# control_boardv15.net
KiCad netlist of a schematic drawn in EAGLE
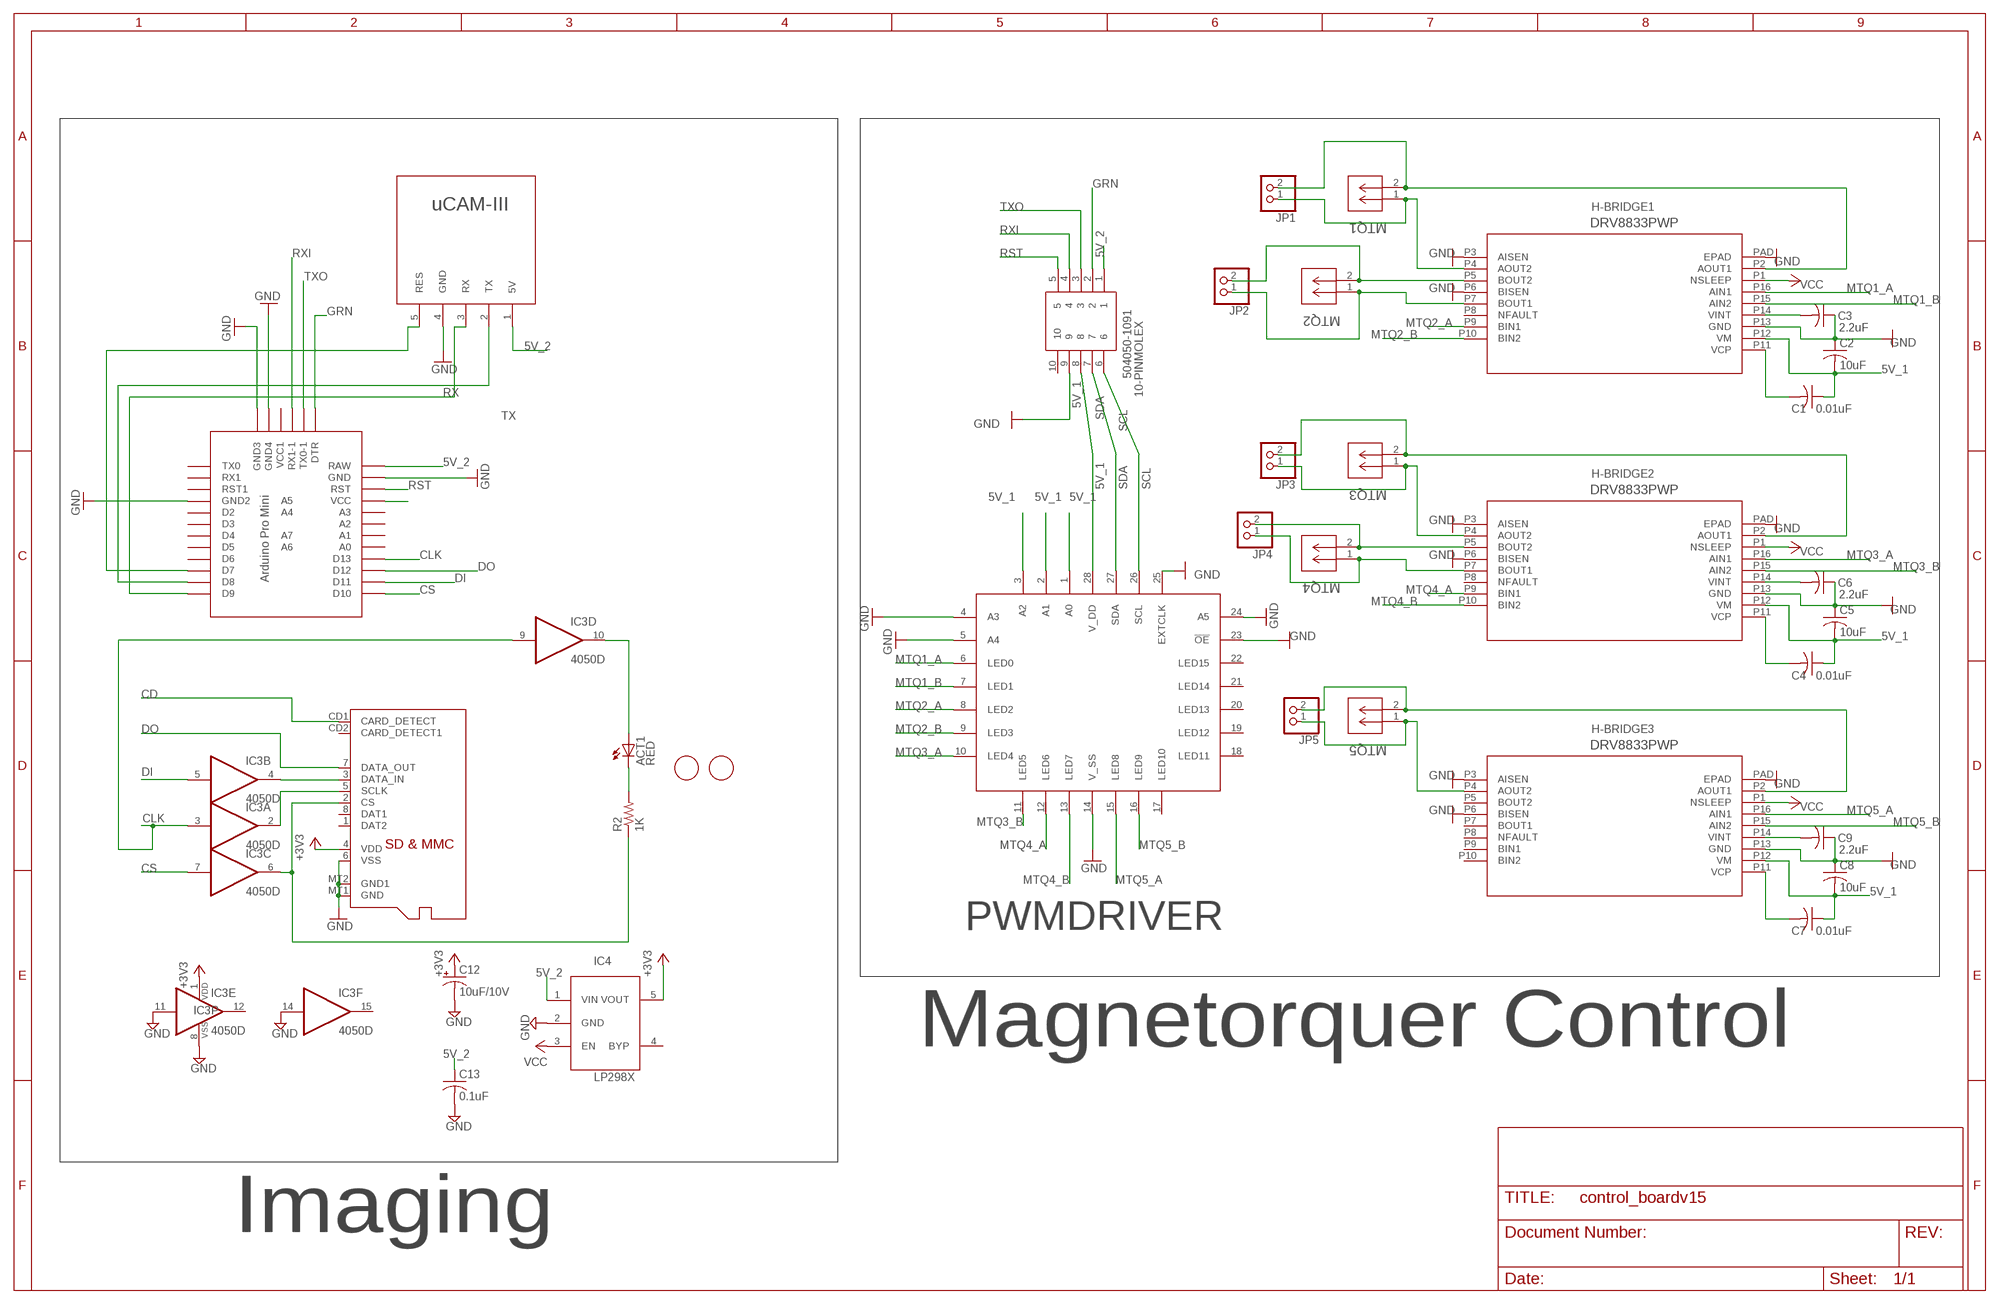
[diagram p0: schematic, sheet 1]

(export (version "E")
  (design (tool "Eeschema 10.0.6"))
  (components
    (comp (ref "10-PINMOLEX")
      (value "504050-1091")
      (footprint "eagle-import:504050-1091")
      (fields (field (name "MOUSER_PART_NUMBER") "538-504050-1091"))
      (libsource (lib "eagle-import") (part "504050-1091"))
    )
    (comp (ref "ACT1")
      (value "RED")
      (footprint "eagle-import:CHIP-LED0805")
      (libsource (lib "eagle-import") (part "LEDCHIP-LED0805"))
    )
    (comp (ref "C1")
      (value "0.01uF")
      (footprint "eagle-import:C0603K")
      (libsource (lib "eagle-import") (part "rcl_334_C-USC0603K"))
    )
    (comp (ref "C2")
      (value "10uF")
      (footprint "eagle-import:C1210K")
      (libsource (lib "eagle-import") (part "rcl_334_C-USC1210K"))
    )
    (comp (ref "C3")
      (value "2.2uF")
      (footprint "eagle-import:C0603K")
      (libsource (lib "eagle-import") (part "rcl_334_C-USC0603K"))
    )
    (comp (ref "C4")
      (value "0.01uF")
      (footprint "eagle-import:C0603K")
      (libsource (lib "eagle-import") (part "rcl_334_C-USC0603K"))
    )
    (comp (ref "C5")
      (value "10uF")
      (footprint "eagle-import:C1210K")
      (libsource (lib "eagle-import") (part "rcl_334_C-USC1210K"))
    )
    (comp (ref "C6")
      (value "2.2uF")
      (footprint "eagle-import:C0603K")
      (libsource (lib "eagle-import") (part "rcl_334_C-USC0603K"))
    )
    (comp (ref "C7")
      (value "0.01uF")
      (footprint "eagle-import:C0603K")
      (libsource (lib "eagle-import") (part "rcl_334_C-USC0603K"))
    )
    (comp (ref "C8")
      (value "10uF")
      (footprint "eagle-import:C1210K")
      (libsource (lib "eagle-import") (part "rcl_334_C-USC1210K"))
    )
    (comp (ref "C9")
      (value "2.2uF")
      (footprint "eagle-import:C0603K")
      (libsource (lib "eagle-import") (part "rcl_334_C-USC0603K"))
    )
    (comp (ref "C12")
      (value "10uF/10V")
      (footprint "eagle-import:A_3216-18R")
      (libsource (lib "eagle-import") (part "CPOL-USA/3216-18R"))
    )
    (comp (ref "C13")
      (value "0.1uF")
      (footprint "eagle-import:C0805K")
      (libsource (lib "eagle-import") (part "C-USC0805K"))
    )
    (comp (ref "H-BRIDGE1")
      (value "DRV8833PWP")
      (footprint "eagle-import:HTSSOP16")
      (libsource (lib "eagle-import") (part "DRV8833PWP"))
    )
    (comp (ref "H-BRIDGE2")
      (value "DRV8833PWP")
      (footprint "eagle-import:HTSSOP16")
      (libsource (lib "eagle-import") (part "DRV8833PWP"))
    )
    (comp (ref "H-BRIDGE3")
      (value "DRV8833PWP")
      (footprint "eagle-import:HTSSOP16")
      (libsource (lib "eagle-import") (part "DRV8833PWP"))
    )
    (comp (ref "IC3")
      (value "4050D")
      (footprint "eagle-import:SO16")
      (libsource (lib "eagle-import") (part "4050D"))
    )
    (comp (ref "IC4")
      (value "LP298XS")
      (footprint "eagle-import:SOT23-5L")
      (libsource (lib "eagle-import") (part "LP298XS"))
    )
    (comp (ref "JP1")
      (value "PINHD-1X2")
      (footprint "eagle-import:1X02")
      (libsource (lib "eagle-import") (part "PINHD-1X2"))
    )
    (comp (ref "JP2")
      (value "PINHD-1X2")
      (footprint "eagle-import:1X02")
      (libsource (lib "eagle-import") (part "PINHD-1X2"))
    )
    (comp (ref "JP3")
      (value "PINHD-1X2")
      (footprint "eagle-import:1X02")
      (libsource (lib "eagle-import") (part "PINHD-1X2"))
    )
    (comp (ref "JP4")
      (value "PINHD-1X2")
      (footprint "eagle-import:1X02")
      (libsource (lib "eagle-import") (part "PINHD-1X2"))
    )
    (comp (ref "JP5")
      (value "PINHD-1X2")
      (footprint "eagle-import:1X02")
      (libsource (lib "eagle-import") (part "PINHD-1X2"))
    )
    (comp (ref "MTQ1")
      (value "DF13C-2P-1.25V(51)")
      (footprint "eagle-import:CON2_1X2_U_DF13")
      (libsource (lib "eagle-import") (part "DF13C-2P-1.25V(51)"))
    )
    (comp (ref "MTQ2")
      (value "DF13C-2P-1.25V(51)")
      (footprint "eagle-import:CON2_1X2_U_DF13")
      (libsource (lib "eagle-import") (part "DF13C-2P-1.25V(51)"))
    )
    (comp (ref "MTQ3")
      (value "DF13C-2P-1.25V(51)")
      (footprint "eagle-import:CON2_1X2_U_DF13")
      (libsource (lib "eagle-import") (part "DF13C-2P-1.25V(51)"))
    )
    (comp (ref "MTQ4")
      (value "DF13C-2P-1.25V(51)")
      (footprint "eagle-import:CON2_1X2_U_DF13")
      (libsource (lib "eagle-import") (part "DF13C-2P-1.25V(51)"))
    )
    (comp (ref "MTQ5")
      (value "DF13C-2P-1.25V(51)")
      (footprint "eagle-import:CON2_1X2_U_DF13")
      (libsource (lib "eagle-import") (part "DF13C-2P-1.25V(51)"))
    )
    (comp (ref "PWMDRIVER")
      (value "PCA9685PW")
      (footprint "eagle-import:TSSOP28")
      (libsource (lib "eagle-import") (part "PCA9685PW"))
    )
    (comp (ref "R2")
      (value "1K")
      (footprint "eagle-import:R0805")
      (libsource (lib "eagle-import") (part "R-US_R0805"))
    )
    (comp (ref "U$2")
      (value "UCAM-III")
      (footprint "eagle-import:UCAM-III")
      (libsource (lib "eagle-import") (part "UCAM-III"))
    )
    (comp (ref "U$6")
      (value "FIDUCIAL")
      (footprint "eagle-import:FIDUCIAL_1MM")
      (libsource (lib "eagle-import") (part "FIDUCIAL"))
    )
    (comp (ref "U$7")
      (value "FIDUCIAL")
      (footprint "eagle-import:FIDUCIAL_1MM")
      (libsource (lib "eagle-import") (part "FIDUCIAL"))
    )
    (comp (ref "U$8")
      (value "PRO-MINI-2")
      (footprint "eagle-import:PRO-MINI-2")
      (libsource (lib "eagle-import") (part "PRO-MINI-2"))
    )
    (comp (ref "X2")
      (value "MICROSD")
      (footprint "eagle-import:MICROSD")
      (libsource (lib "eagle-import") (part "MICROSD"))
    )
  )
  (nets
    (net (code "1") (name "+3V3") (class "Default")
      (node (ref "C12") (pin "+") (pinfunction "+_+") (pintype "passive"))
      (node (ref "IC3") (pin "1") (pinfunction "VDD_1") (pintype "power_in"))
      (node (ref "IC4") (pin "5") (pinfunction "VOUT_5") (pintype "bidirectional"))
      (node (ref "X2") (pin "4") (pinfunction "VDD_4") (pintype "power_in"))
    )
    (net (code "2") (name "/5V_1") (class "Default")
      (node (ref "10-PINMOLEX") (pin "8") (pinfunction "8_8") (pintype "bidirectional"))
      (node (ref "C1") (pin "1") (pinfunction "1_1") (pintype "passive"))
      (node (ref "C2") (pin "2") (pinfunction "2_2") (pintype "passive"))
      (node (ref "C4") (pin "1") (pinfunction "1_1") (pintype "passive"))
      (node (ref "C5") (pin "2") (pinfunction "2_2") (pintype "passive"))
      (node (ref "C7") (pin "1") (pinfunction "1_1") (pintype "passive"))
      (node (ref "C8") (pin "2") (pinfunction "2_2") (pintype "passive"))
      (node (ref "H-BRIDGE1") (pin "P12") (pinfunction "VM_P12") (pintype "power_in"))
      (node (ref "H-BRIDGE2") (pin "P12") (pinfunction "VM_P12") (pintype "power_in"))
      (node (ref "H-BRIDGE3") (pin "P12") (pinfunction "VM_P12") (pintype "power_in"))
      (node (ref "PWMDRIVER") (pin "1") (pinfunction "A0_1") (pintype "bidirectional"))
      (node (ref "PWMDRIVER") (pin "2") (pinfunction "A1_2") (pintype "bidirectional"))
      (node (ref "PWMDRIVER") (pin "28") (pinfunction "V_DD_28") (pintype "bidirectional"))
      (node (ref "PWMDRIVER") (pin "3") (pinfunction "A2_3") (pintype "bidirectional"))
    )
    (net (code "3") (name "/5V_2") (class "Default")
      (node (ref "10-PINMOLEX") (pin "1") (pinfunction "1_1") (pintype "bidirectional"))
      (node (ref "C13") (pin "1") (pinfunction "1_1") (pintype "passive"))
      (node (ref "IC4") (pin "1") (pinfunction "VIN_1") (pintype "bidirectional"))
      (node (ref "U$2") (pin "1") (pinfunction "5V_1") (pintype "bidirectional"))
      (node (ref "U$8") (pin "RAW") (pinfunction "RAW_RAW") (pintype "bidirectional"))
    )
    (net (code "4") (name "/CD") (class "Default")
      (node (ref "X2") (pin "CD1") (pinfunction "CARD_DETECT_CD1") (pintype "passive"))
    )
    (net (code "5") (name "/CLK") (class "Default")
      (node (ref "IC3") (pin "3") (pinfunction "I_3") (pintype "input"))
      (node (ref "IC3") (pin "9") (pinfunction "I_9") (pintype "input"))
      (node (ref "U$8") (pin "D13") (pinfunction "D13_D13") (pintype "bidirectional"))
    )
    (net (code "6") (name "/CS") (class "Default")
      (node (ref "IC3") (pin "7") (pinfunction "I_7") (pintype "input"))
      (node (ref "U$8") (pin "D10") (pinfunction "D10_D10") (pintype "bidirectional"))
    )
    (net (code "7") (name "/DI") (class "Default")
      (node (ref "IC3") (pin "5") (pinfunction "I_5") (pintype "input"))
      (node (ref "U$8") (pin "D11") (pinfunction "D11_D11") (pintype "bidirectional"))
    )
    (net (code "8") (name "/DO") (class "Default")
      (node (ref "U$8") (pin "D12") (pinfunction "D12_D12") (pintype "bidirectional"))
      (node (ref "X2") (pin "7") (pinfunction "DATA_OUT_7") (pintype "output"))
    )
    (net (code "9") (name "/GRN") (class "Default")
      (node (ref "10-PINMOLEX") (pin "2") (pinfunction "2_2") (pintype "bidirectional"))
      (node (ref "U$8") (pin "DTR") (pinfunction "DTR_DTR") (pintype "bidirectional"))
    )
    (net (code "10") (name "/MTQ1_A") (class "Default")
      (node (ref "H-BRIDGE1") (pin "P16") (pinfunction "AIN1_P16") (pintype "input"))
      (node (ref "PWMDRIVER") (pin "6") (pinfunction "LED0_6") (pintype "bidirectional"))
    )
    (net (code "11") (name "/MTQ1_B") (class "Default")
      (node (ref "H-BRIDGE1") (pin "P15") (pinfunction "AIN2_P15") (pintype "input"))
      (node (ref "PWMDRIVER") (pin "7") (pinfunction "LED1_7") (pintype "bidirectional"))
    )
    (net (code "12") (name "/MTQ2_A") (class "Default")
      (node (ref "H-BRIDGE1") (pin "P9") (pinfunction "BIN1_P9") (pintype "input"))
      (node (ref "PWMDRIVER") (pin "8") (pinfunction "LED2_8") (pintype "bidirectional"))
    )
    (net (code "13") (name "/MTQ2_B") (class "Default")
      (node (ref "H-BRIDGE1") (pin "P10") (pinfunction "BIN2_P10") (pintype "input"))
      (node (ref "PWMDRIVER") (pin "9") (pinfunction "LED3_9") (pintype "bidirectional"))
    )
    (net (code "14") (name "/MTQ3_A") (class "Default")
      (node (ref "H-BRIDGE2") (pin "P16") (pinfunction "AIN1_P16") (pintype "input"))
      (node (ref "PWMDRIVER") (pin "10") (pinfunction "LED4_10") (pintype "bidirectional"))
    )
    (net (code "15") (name "/MTQ3_B") (class "Default")
      (node (ref "H-BRIDGE2") (pin "P15") (pinfunction "AIN2_P15") (pintype "input"))
      (node (ref "PWMDRIVER") (pin "11") (pinfunction "LED5_11") (pintype "bidirectional"))
    )
    (net (code "16") (name "/MTQ4_A") (class "Default")
      (node (ref "H-BRIDGE2") (pin "P9") (pinfunction "BIN1_P9") (pintype "input"))
      (node (ref "PWMDRIVER") (pin "12") (pinfunction "LED6_12") (pintype "bidirectional"))
    )
    (net (code "17") (name "/MTQ4_B") (class "Default")
      (node (ref "H-BRIDGE2") (pin "P10") (pinfunction "BIN2_P10") (pintype "input"))
      (node (ref "PWMDRIVER") (pin "13") (pinfunction "LED7_13") (pintype "bidirectional"))
    )
    (net (code "18") (name "/MTQ5_A") (class "Default")
      (node (ref "H-BRIDGE3") (pin "P16") (pinfunction "AIN1_P16") (pintype "input"))
      (node (ref "PWMDRIVER") (pin "15") (pinfunction "LED8_15") (pintype "bidirectional"))
    )
    (net (code "19") (name "/MTQ5_B") (class "Default")
      (node (ref "H-BRIDGE3") (pin "P15") (pinfunction "AIN2_P15") (pintype "input"))
      (node (ref "PWMDRIVER") (pin "16") (pinfunction "LED9_16") (pintype "bidirectional"))
    )
    (net (code "20") (name "/RST") (class "Default")
      (node (ref "10-PINMOLEX") (pin "5") (pinfunction "5_5") (pintype "bidirectional"))
      (node (ref "U$8") (pin "RST") (pinfunction "RST_RST") (pintype "bidirectional"))
    )
    (net (code "21") (name "/RX") (class "Default")
      (node (ref "U$2") (pin "3") (pinfunction "RX_3") (pintype "bidirectional"))
      (node (ref "U$8") (pin "D9") (pinfunction "D9_D9") (pintype "bidirectional"))
    )
    (net (code "22") (name "/RXI") (class "Default")
      (node (ref "10-PINMOLEX") (pin "4") (pinfunction "4_4") (pintype "bidirectional"))
      (node (ref "U$8") (pin "RX1-1") (pinfunction "RX1-1_RX1-1") (pintype "bidirectional"))
    )
    (net (code "23") (name "/SCL") (class "Default")
      (node (ref "10-PINMOLEX") (pin "6") (pinfunction "6_6") (pintype "bidirectional"))
      (node (ref "PWMDRIVER") (pin "26") (pinfunction "SCL_26") (pintype "bidirectional"))
    )
    (net (code "24") (name "/SDA") (class "Default")
      (node (ref "10-PINMOLEX") (pin "7") (pinfunction "7_7") (pintype "bidirectional"))
      (node (ref "PWMDRIVER") (pin "27") (pinfunction "SDA_27") (pintype "bidirectional"))
    )
    (net (code "25") (name "/TX") (class "Default")
      (node (ref "U$2") (pin "2") (pinfunction "TX_2") (pintype "bidirectional"))
      (node (ref "U$8") (pin "D8") (pinfunction "D8_D8") (pintype "bidirectional"))
    )
    (net (code "26") (name "/TXO") (class "Default")
      (node (ref "10-PINMOLEX") (pin "3") (pinfunction "3_3") (pintype "bidirectional"))
      (node (ref "U$8") (pin "TX0-1") (pinfunction "TX0-1_TX0-1") (pintype "bidirectional"))
    )
    (net (code "27") (name "GND") (class "Default")
      (node (ref "10-PINMOLEX") (pin "9") (pinfunction "9_9") (pintype "bidirectional"))
      (node (ref "C12") (pin "-") (pinfunction "-_-") (pintype "passive"))
      (node (ref "C13") (pin "2") (pinfunction "2_2") (pintype "passive"))
      (node (ref "C2") (pin "1") (pinfunction "1_1") (pintype "passive"))
      (node (ref "C3") (pin "1") (pinfunction "1_1") (pintype "passive"))
      (node (ref "C5") (pin "1") (pinfunction "1_1") (pintype "passive"))
      (node (ref "C6") (pin "1") (pinfunction "1_1") (pintype "passive"))
      (node (ref "C8") (pin "1") (pinfunction "1_1") (pintype "passive"))
      (node (ref "C9") (pin "1") (pinfunction "1_1") (pintype "passive"))
      (node (ref "H-BRIDGE1") (pin "P13") (pinfunction "GND_P13") (pintype "power_in"))
      (node (ref "H-BRIDGE1") (pin "P3") (pinfunction "AISEN_P3") (pintype "bidirectional"))
      (node (ref "H-BRIDGE1") (pin "P6") (pinfunction "BISEN_P6") (pintype "bidirectional"))
      (node (ref "H-BRIDGE1") (pin "PAD") (pinfunction "EPAD_PAD") (pintype "passive"))
      (node (ref "H-BRIDGE2") (pin "P13") (pinfunction "GND_P13") (pintype "power_in"))
      (node (ref "H-BRIDGE2") (pin "P3") (pinfunction "AISEN_P3") (pintype "bidirectional"))
      (node (ref "H-BRIDGE2") (pin "P6") (pinfunction "BISEN_P6") (pintype "bidirectional"))
      (node (ref "H-BRIDGE2") (pin "PAD") (pinfunction "EPAD_PAD") (pintype "passive"))
      (node (ref "H-BRIDGE3") (pin "P13") (pinfunction "GND_P13") (pintype "power_in"))
      (node (ref "H-BRIDGE3") (pin "P3") (pinfunction "AISEN_P3") (pintype "bidirectional"))
      (node (ref "H-BRIDGE3") (pin "P6") (pinfunction "BISEN_P6") (pintype "bidirectional"))
      (node (ref "H-BRIDGE3") (pin "PAD") (pinfunction "EPAD_PAD") (pintype "passive"))
      (node (ref "IC3") (pin "11") (pinfunction "I_11") (pintype "input"))
      (node (ref "IC3") (pin "14") (pinfunction "I_14") (pintype "input"))
      (node (ref "IC3") (pin "8") (pinfunction "VSS_8") (pintype "power_in"))
      (node (ref "IC4") (pin "2") (pinfunction "GND_2") (pintype "bidirectional"))
      (node (ref "PWMDRIVER") (pin "14") (pinfunction "V_SS_14") (pintype "bidirectional"))
      (node (ref "PWMDRIVER") (pin "23") (pinfunction "~{OE}_23") (pintype "bidirectional"))
      (node (ref "PWMDRIVER") (pin "24") (pinfunction "A5_24") (pintype "bidirectional"))
      (node (ref "PWMDRIVER") (pin "25") (pinfunction "EXTCLK_25") (pintype "bidirectional"))
      (node (ref "PWMDRIVER") (pin "4") (pinfunction "A3_4") (pintype "bidirectional"))
      (node (ref "PWMDRIVER") (pin "5") (pinfunction "A4_5") (pintype "bidirectional"))
      (node (ref "U$2") (pin "4") (pinfunction "GND_4") (pintype "bidirectional"))
      (node (ref "U$8") (pin "GND") (pinfunction "GND_GND") (pintype "bidirectional"))
      (node (ref "U$8") (pin "GND1") (pinfunction "GND2_GND1") (pintype "bidirectional"))
      (node (ref "U$8") (pin "GND2") (pinfunction "GND3_GND2") (pintype "bidirectional"))
      (node (ref "U$8") (pin "GND3") (pinfunction "GND4_GND3") (pintype "bidirectional"))
      (node (ref "X2") (pin "6") (pinfunction "VSS_6") (pintype "power_in"))
      (node (ref "X2") (pin "MT1") (pinfunction "GND_MT1") (pintype "power_in"))
      (node (ref "X2") (pin "MT2") (pinfunction "GND1_MT2") (pintype "power_in"))
    )
    (net (code "28") (name "Net-(ACT1-PadC)") (class "Default")
      (node (ref "ACT1") (pin "C") (pinfunction "C_C") (pintype "passive"))
      (node (ref "R2") (pin "2") (pinfunction "2_2") (pintype "passive"))
    )
    (net (code "29") (name "Net-(H-BRIDGE1-AOUT1)") (class "Default")
      (node (ref "H-BRIDGE1") (pin "P2") (pinfunction "AOUT1_P2") (pintype "output"))
      (node (ref "JP1") (pin "2") (pinfunction "2_2") (pintype "passive"))
      (node (ref "MTQ1") (pin "2") (pinfunction "2_2") (pintype "passive"))
    )
    (net (code "30") (name "Net-(H-BRIDGE1-AOUT2)") (class "Default")
      (node (ref "H-BRIDGE1") (pin "P4") (pinfunction "AOUT2_P4") (pintype "output"))
      (node (ref "JP1") (pin "1") (pinfunction "1_1") (pintype "passive"))
      (node (ref "MTQ1") (pin "1") (pinfunction "1_1") (pintype "passive"))
    )
    (net (code "31") (name "Net-(H-BRIDGE1-BOUT1)") (class "Default")
      (node (ref "H-BRIDGE1") (pin "P7") (pinfunction "BOUT1_P7") (pintype "output"))
      (node (ref "JP2") (pin "1") (pinfunction "1_1") (pintype "passive"))
      (node (ref "MTQ2") (pin "1") (pinfunction "1_1") (pintype "passive"))
    )
    (net (code "32") (name "Net-(H-BRIDGE1-BOUT2)") (class "Default")
      (node (ref "H-BRIDGE1") (pin "P5") (pinfunction "BOUT2_P5") (pintype "output"))
      (node (ref "JP2") (pin "2") (pinfunction "2_2") (pintype "passive"))
      (node (ref "MTQ2") (pin "2") (pinfunction "2_2") (pintype "passive"))
    )
    (net (code "33") (name "Net-(H-BRIDGE1-VCP)") (class "Default")
      (node (ref "C1") (pin "2") (pinfunction "2_2") (pintype "passive"))
      (node (ref "H-BRIDGE1") (pin "P11") (pinfunction "VCP_P11") (pintype "bidirectional"))
    )
    (net (code "34") (name "Net-(H-BRIDGE1-VINT)") (class "Default")
      (node (ref "C3") (pin "2") (pinfunction "2_2") (pintype "passive"))
      (node (ref "H-BRIDGE1") (pin "P14") (pinfunction "VINT_P14") (pintype "power_in"))
    )
    (net (code "35") (name "Net-(H-BRIDGE2-AOUT1)") (class "Default")
      (node (ref "H-BRIDGE2") (pin "P2") (pinfunction "AOUT1_P2") (pintype "output"))
      (node (ref "JP3") (pin "2") (pinfunction "2_2") (pintype "passive"))
      (node (ref "MTQ3") (pin "2") (pinfunction "2_2") (pintype "passive"))
    )
    (net (code "36") (name "Net-(H-BRIDGE2-AOUT2)") (class "Default")
      (node (ref "H-BRIDGE2") (pin "P4") (pinfunction "AOUT2_P4") (pintype "output"))
      (node (ref "JP3") (pin "1") (pinfunction "1_1") (pintype "passive"))
      (node (ref "MTQ3") (pin "1") (pinfunction "1_1") (pintype "passive"))
    )
    (net (code "37") (name "Net-(H-BRIDGE2-BOUT1)") (class "Default")
      (node (ref "H-BRIDGE2") (pin "P7") (pinfunction "BOUT1_P7") (pintype "output"))
      (node (ref "JP4") (pin "1") (pinfunction "1_1") (pintype "passive"))
      (node (ref "MTQ4") (pin "1") (pinfunction "1_1") (pintype "passive"))
    )
    (net (code "38") (name "Net-(H-BRIDGE2-BOUT2)") (class "Default")
      (node (ref "H-BRIDGE2") (pin "P5") (pinfunction "BOUT2_P5") (pintype "output"))
      (node (ref "JP4") (pin "2") (pinfunction "2_2") (pintype "passive"))
      (node (ref "MTQ4") (pin "2") (pinfunction "2_2") (pintype "passive"))
    )
    (net (code "39") (name "Net-(H-BRIDGE2-VCP)") (class "Default")
      (node (ref "C4") (pin "2") (pinfunction "2_2") (pintype "passive"))
      (node (ref "H-BRIDGE2") (pin "P11") (pinfunction "VCP_P11") (pintype "bidirectional"))
    )
    (net (code "40") (name "Net-(H-BRIDGE2-VINT)") (class "Default")
      (node (ref "C6") (pin "2") (pinfunction "2_2") (pintype "passive"))
      (node (ref "H-BRIDGE2") (pin "P14") (pinfunction "VINT_P14") (pintype "power_in"))
    )
    (net (code "41") (name "Net-(H-BRIDGE3-AOUT1)") (class "Default")
      (node (ref "H-BRIDGE3") (pin "P2") (pinfunction "AOUT1_P2") (pintype "output"))
      (node (ref "JP5") (pin "2") (pinfunction "2_2") (pintype "passive"))
      (node (ref "MTQ5") (pin "2") (pinfunction "2_2") (pintype "passive"))
    )
    (net (code "42") (name "Net-(H-BRIDGE3-AOUT2)") (class "Default")
      (node (ref "H-BRIDGE3") (pin "P4") (pinfunction "AOUT2_P4") (pintype "output"))
      (node (ref "JP5") (pin "1") (pinfunction "1_1") (pintype "passive"))
      (node (ref "MTQ5") (pin "1") (pinfunction "1_1") (pintype "passive"))
    )
    (net (code "43") (name "Net-(H-BRIDGE3-VCP)") (class "Default")
      (node (ref "C7") (pin "2") (pinfunction "2_2") (pintype "passive"))
      (node (ref "H-BRIDGE3") (pin "P11") (pinfunction "VCP_P11") (pintype "bidirectional"))
    )
    (net (code "44") (name "Net-(H-BRIDGE3-VINT)") (class "Default")
      (node (ref "C9") (pin "2") (pinfunction "2_2") (pintype "passive"))
      (node (ref "H-BRIDGE3") (pin "P14") (pinfunction "VINT_P14") (pintype "power_in"))
    )
    (net (code "45") (name "Net-(IC3A-O)") (class "Default")
      (node (ref "IC3") (pin "2") (pinfunction "O_2") (pintype "output"))
      (node (ref "X2") (pin "5") (pinfunction "SCLK_5") (pintype "input"))
    )
    (net (code "46") (name "Net-(IC3B-O)") (class "Default")
      (node (ref "IC3") (pin "4") (pinfunction "O_4") (pintype "output"))
      (node (ref "X2") (pin "3") (pinfunction "DATA_IN_3") (pintype "input"))
    )
    (net (code "47") (name "Net-(IC3C-O)") (class "Default")
      (node (ref "IC3") (pin "6") (pinfunction "O_6") (pintype "output"))
      (node (ref "R2") (pin "1") (pinfunction "1_1") (pintype "passive"))
      (node (ref "X2") (pin "2") (pinfunction "CS_2") (pintype "input"))
    )
    (net (code "48") (name "Net-(IC3D-O)") (class "Default")
      (node (ref "ACT1") (pin "A") (pinfunction "A_A") (pintype "passive"))
      (node (ref "IC3") (pin "10") (pinfunction "O_10") (pintype "output"))
    )
    (net (code "49") (name "Net-(U$2-RES)") (class "Default")
      (node (ref "U$2") (pin "5") (pinfunction "RES_5") (pintype "bidirectional"))
      (node (ref "U$8") (pin "D7") (pinfunction "D7_D7") (pintype "bidirectional"))
    )
    (net (code "50") (name "VCC") (class "Default")
      (node (ref "H-BRIDGE1") (pin "P1") (pinfunction "NSLEEP_P1") (pintype "input"))
      (node (ref "H-BRIDGE2") (pin "P1") (pinfunction "NSLEEP_P1") (pintype "input"))
      (node (ref "H-BRIDGE3") (pin "P1") (pinfunction "NSLEEP_P1") (pintype "input"))
      (node (ref "IC4") (pin "3") (pinfunction "EN_3") (pintype "bidirectional"))
    )
    (net (code "51") (name "unconnected-(10-PINMOLEX-Pad10)") (class "Default")
      (node (ref "10-PINMOLEX") (pin "10") (pinfunction "10_10") (pintype "bidirectional"))
    )
    (net (code "52") (name "unconnected-(H-BRIDGE1-NFAULT-PadP8)") (class "Default")
      (node (ref "H-BRIDGE1") (pin "P8") (pinfunction "NFAULT_P8") (pintype "output"))
    )
    (net (code "53") (name "unconnected-(H-BRIDGE2-NFAULT-PadP8)") (class "Default")
      (node (ref "H-BRIDGE2") (pin "P8") (pinfunction "NFAULT_P8") (pintype "output"))
    )
    (net (code "54") (name "unconnected-(H-BRIDGE3-BIN1-PadP9)") (class "Default")
      (node (ref "H-BRIDGE3") (pin "P9") (pinfunction "BIN1_P9") (pintype "input"))
    )
    (net (code "55") (name "unconnected-(H-BRIDGE3-BIN2-PadP10)") (class "Default")
      (node (ref "H-BRIDGE3") (pin "P10") (pinfunction "BIN2_P10") (pintype "input"))
    )
    (net (code "56") (name "unconnected-(H-BRIDGE3-BOUT1-PadP7)") (class "Default")
      (node (ref "H-BRIDGE3") (pin "P7") (pinfunction "BOUT1_P7") (pintype "output"))
    )
    (net (code "57") (name "unconnected-(H-BRIDGE3-BOUT2-PadP5)") (class "Default")
      (node (ref "H-BRIDGE3") (pin "P5") (pinfunction "BOUT2_P5") (pintype "output"))
    )
    (net (code "58") (name "unconnected-(H-BRIDGE3-NFAULT-PadP8)") (class "Default")
      (node (ref "H-BRIDGE3") (pin "P8") (pinfunction "NFAULT_P8") (pintype "output"))
    )
    (net (code "59") (name "unconnected-(IC3E-O-Pad12)") (class "Default")
      (node (ref "IC3") (pin "12") (pinfunction "O_12") (pintype "output"))
    )
    (net (code "60") (name "unconnected-(IC3F-O-Pad15)") (class "Default")
      (node (ref "IC3") (pin "15") (pinfunction "O_15") (pintype "output"))
    )
    (net (code "61") (name "unconnected-(IC4-BYP-Pad4)") (class "Default")
      (node (ref "IC4") (pin "4") (pinfunction "BYP_4") (pintype "bidirectional"))
    )
    (net (code "62") (name "unconnected-(PWMDRIVER-LED10-Pad17)") (class "Default")
      (node (ref "PWMDRIVER") (pin "17") (pinfunction "LED10_17") (pintype "bidirectional"))
    )
    (net (code "63") (name "unconnected-(PWMDRIVER-LED11-Pad18)") (class "Default")
      (node (ref "PWMDRIVER") (pin "18") (pinfunction "LED11_18") (pintype "bidirectional"))
    )
    (net (code "64") (name "unconnected-(PWMDRIVER-LED12-Pad19)") (class "Default")
      (node (ref "PWMDRIVER") (pin "19") (pinfunction "LED12_19") (pintype "bidirectional"))
    )
    (net (code "65") (name "unconnected-(PWMDRIVER-LED13-Pad20)") (class "Default")
      (node (ref "PWMDRIVER") (pin "20") (pinfunction "LED13_20") (pintype "bidirectional"))
    )
    (net (code "66") (name "unconnected-(PWMDRIVER-LED14-Pad21)") (class "Default")
      (node (ref "PWMDRIVER") (pin "21") (pinfunction "LED14_21") (pintype "bidirectional"))
    )
    (net (code "67") (name "unconnected-(PWMDRIVER-LED15-Pad22)") (class "Default")
      (node (ref "PWMDRIVER") (pin "22") (pinfunction "LED15_22") (pintype "bidirectional"))
    )
    (net (code "68") (name "unconnected-(U$8-PadA0)") (class "Default")
      (node (ref "U$8") (pin "A0") (pinfunction "A0_A0") (pintype "bidirectional"))
    )
    (net (code "69") (name "unconnected-(U$8-PadA1)") (class "Default")
      (node (ref "U$8") (pin "A1") (pinfunction "A1_A1") (pintype "bidirectional"))
    )
    (net (code "70") (name "unconnected-(U$8-PadA2)") (class "Default")
      (node (ref "U$8") (pin "A2") (pinfunction "A2_A2") (pintype "bidirectional"))
    )
    (net (code "71") (name "unconnected-(U$8-PadA3)") (class "Default")
      (node (ref "U$8") (pin "A3") (pinfunction "A3_A3") (pintype "bidirectional"))
    )
    (net (code "72") (name "unconnected-(U$8-PadA4)") (class "Default")
      (node (ref "U$8") (pin "A4") (pinfunction "A4_A4") (pintype "bidirectional"))
    )
    (net (code "73") (name "unconnected-(U$8-PadA5)") (class "Default")
      (node (ref "U$8") (pin "A5") (pinfunction "A5_A5") (pintype "bidirectional"))
    )
    (net (code "74") (name "unconnected-(U$8-PadA6)") (class "Default")
      (node (ref "U$8") (pin "A6") (pinfunction "A6_A6") (pintype "bidirectional"))
    )
    (net (code "75") (name "unconnected-(U$8-PadA7)") (class "Default")
      (node (ref "U$8") (pin "A7") (pinfunction "A7_A7") (pintype "bidirectional"))
    )
    (net (code "76") (name "unconnected-(U$8-PadD2)") (class "Default")
      (node (ref "U$8") (pin "D2") (pinfunction "D2_D2") (pintype "bidirectional"))
    )
    (net (code "77") (name "unconnected-(U$8-PadD3)") (class "Default")
      (node (ref "U$8") (pin "D3") (pinfunction "D3_D3") (pintype "bidirectional"))
    )
    (net (code "78") (name "unconnected-(U$8-PadD4)") (class "Default")
      (node (ref "U$8") (pin "D4") (pinfunction "D4_D4") (pintype "bidirectional"))
    )
    (net (code "79") (name "unconnected-(U$8-PadD5)") (class "Default")
      (node (ref "U$8") (pin "D5") (pinfunction "D5_D5") (pintype "bidirectional"))
    )
    (net (code "80") (name "unconnected-(U$8-PadD6)") (class "Default")
      (node (ref "U$8") (pin "D6") (pinfunction "D6_D6") (pintype "bidirectional"))
    )
    (net (code "81") (name "unconnected-(U$8-PadRST1)") (class "Default")
      (node (ref "U$8") (pin "RST1") (pinfunction "RST1_RST1") (pintype "bidirectional"))
    )
    (net (code "82") (name "unconnected-(U$8-PadRX1)") (class "Default")
      (node (ref "U$8") (pin "RX1") (pinfunction "RX1_RX1") (pintype "bidirectional"))
    )
    (net (code "83") (name "unconnected-(U$8-PadTX0)") (class "Default")
      (node (ref "U$8") (pin "TX0") (pinfunction "TX0_TX0") (pintype "bidirectional"))
    )
    (net (code "84") (name "unconnected-(U$8-PadVCC)") (class "Default")
      (node (ref "U$8") (pin "VCC") (pinfunction "VCC_VCC") (pintype "bidirectional"))
    )
    (net (code "85") (name "unconnected-(U$8-PadVCC1)") (class "Default")
      (node (ref "U$8") (pin "VCC1") (pinfunction "VCC1_VCC1") (pintype "bidirectional"))
    )
    (net (code "86") (name "unconnected-(X2-CARD_DETECT1-PadCD2)") (class "Default")
      (node (ref "X2") (pin "CD2") (pinfunction "CARD_DETECT1_CD2") (pintype "passive"))
    )
    (net (code "87") (name "unconnected-(X2-DAT1-Pad8)") (class "Default")
      (node (ref "X2") (pin "8") (pinfunction "DAT1_8") (pintype "bidirectional"))
    )
    (net (code "88") (name "unconnected-(X2-DAT2-Pad1)") (class "Default")
      (node (ref "X2") (pin "1") (pinfunction "DAT2_1") (pintype "bidirectional"))
    )
  )
)
